# PiCam_Switch_1_2.net
KiCad netlist of a schematic drawn in EAGLE
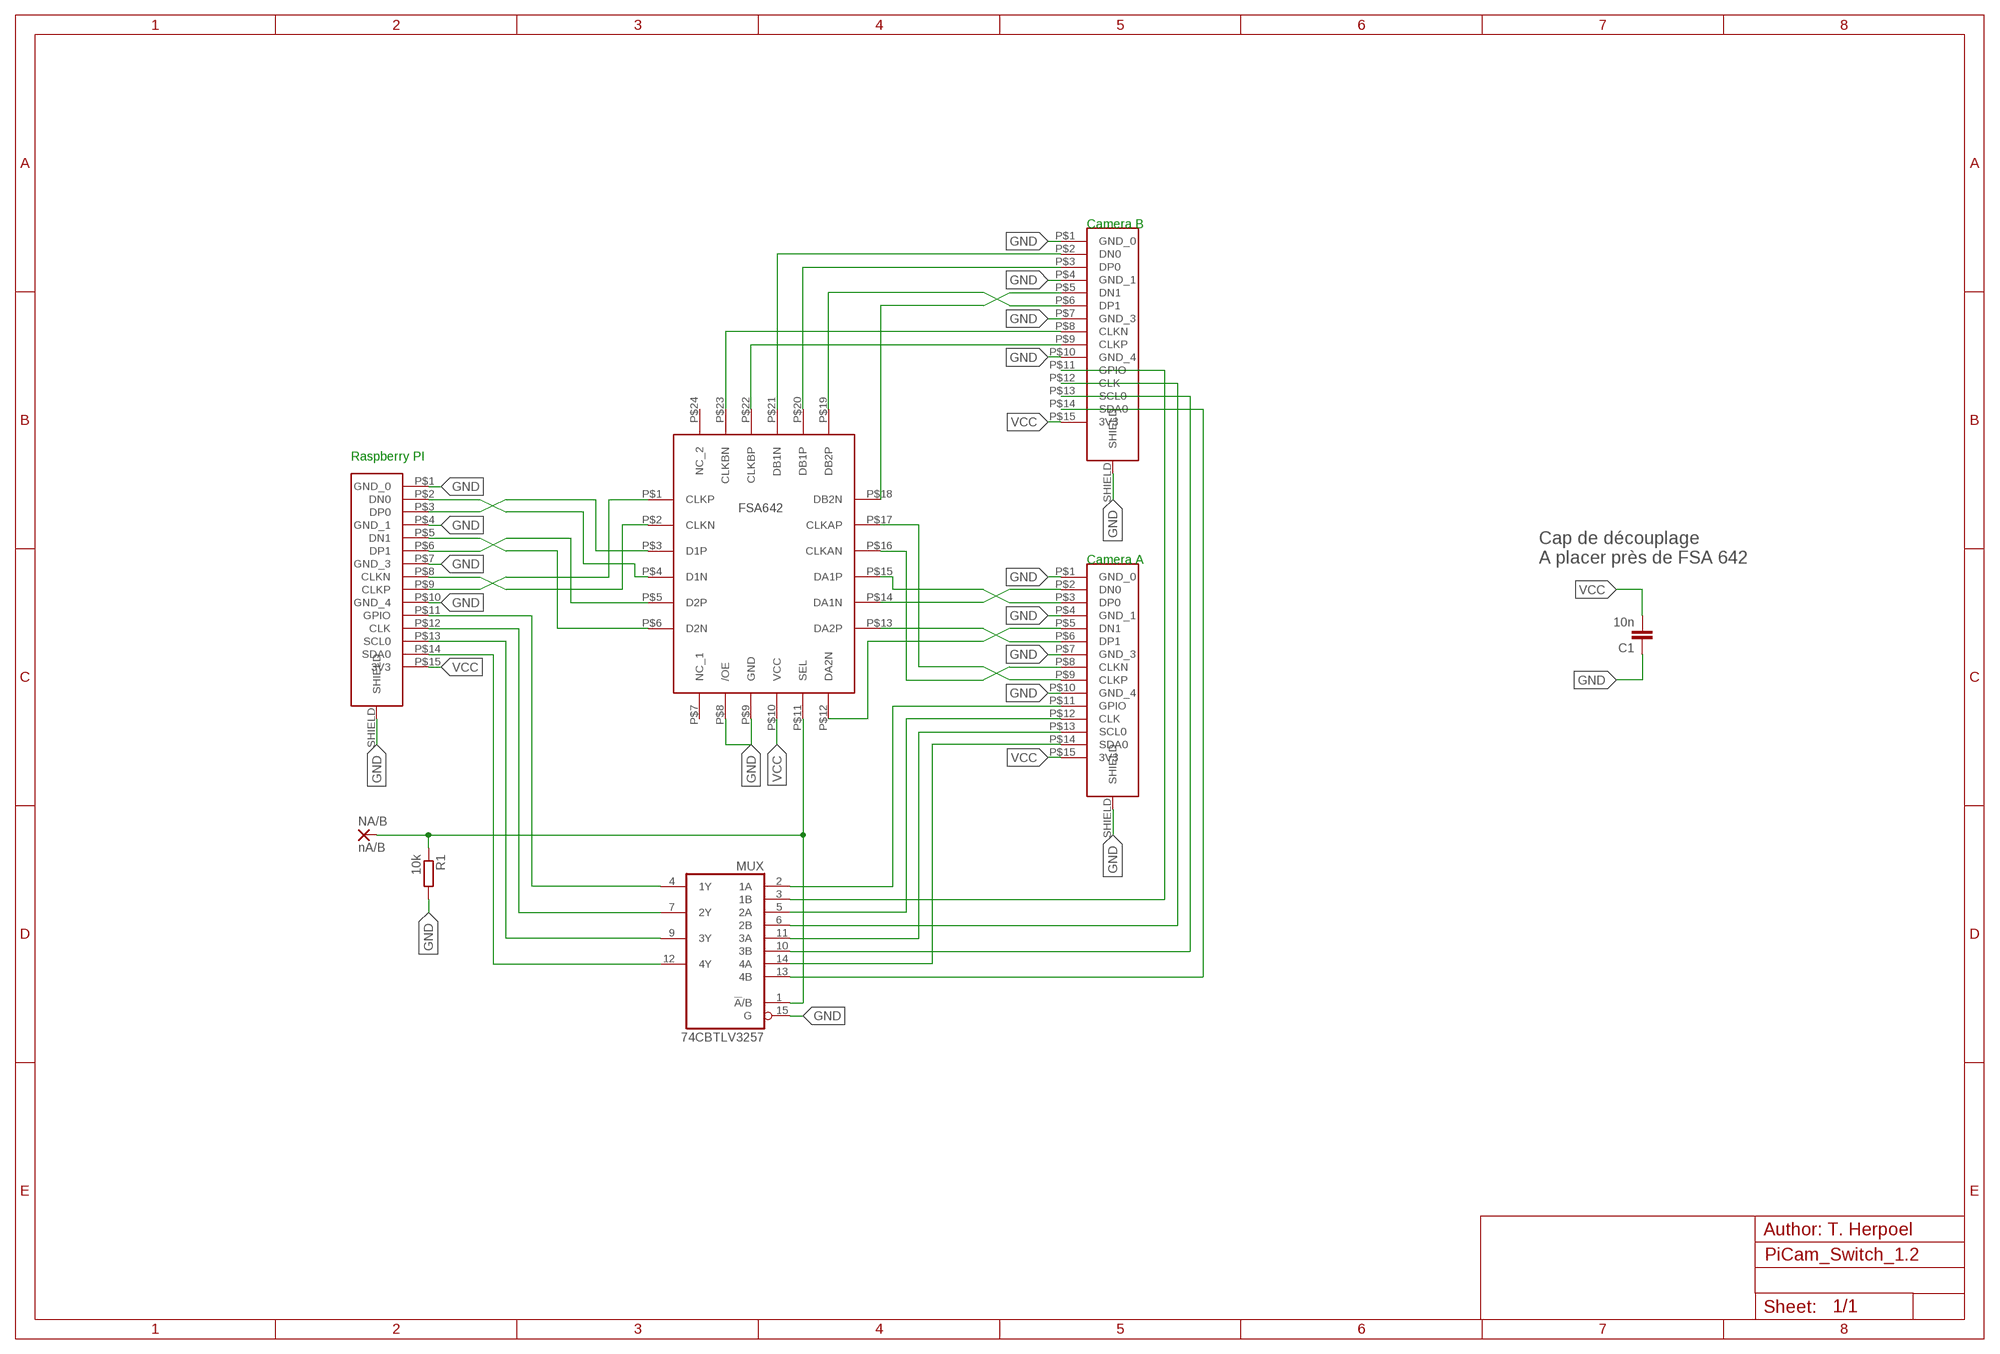
[diagram p0: schematic, sheet 1]

(export (version "E")
  (design (tool "Eeschema 10.0.6"))
  (components
    (comp (ref "C1")
      (value "10n")
      (footprint "eagle-import:C1206")
      (libsource (lib "eagle-import") (part "C-EUC1206"))
    )
    (comp (ref "CAM_A")
      (value "PICAM")
      (footprint "eagle-import:FPC-CONN-15-SMD")
      (libsource (lib "eagle-import") (part "PICAM"))
    )
    (comp (ref "CAM_B")
      (value "PICAM")
      (footprint "eagle-import:FPC-CONN-15-SMD")
      (libsource (lib "eagle-import") (part "PICAM"))
    )
    (comp (ref "MUX")
      (value "74CBTLV3257")
      (footprint "eagle-import:SO16")
      (libsource (lib "eagle-import") (part "74157DHCT"))
    )
    (comp (ref "NA/B")
      (value "nA/B")
      (footprint "eagle-import:SMD1,27-2,54")
      (libsource (lib "eagle-import") (part "SMD2"))
    )
    (comp (ref "R1")
      (value "10k")
      (footprint "eagle-import:R1206")
      (libsource (lib "eagle-import") (part "R-EU_R1206"))
    )
    (comp (ref "RPI")
      (value "PICAM")
      (footprint "eagle-import:FPC-CONN-15-SMD")
      (libsource (lib "eagle-import") (part "PICAM"))
    )
    (comp (ref "U$1")
      (value "FSA642")
      (footprint "eagle-import:UMLP-24")
      (libsource (lib "eagle-import") (part "FSA642"))
    )
  )
  (nets
    (net (code "1") (name "GND") (class "Default")
      (node (ref "C1") (pin "1") (pinfunction "1_1") (pintype "passive"))
      (node (ref "CAM_A") (pin "P$1") (pinfunction "GND_0_P$1") (pintype "bidirectional"))
      (node (ref "CAM_A") (pin "P$10") (pinfunction "GND_4_P$10") (pintype "bidirectional"))
      (node (ref "CAM_A") (pin "P$4") (pinfunction "GND_1_P$4") (pintype "bidirectional"))
      (node (ref "CAM_A") (pin "P$7") (pinfunction "GND_3_P$7") (pintype "bidirectional"))
      (node (ref "CAM_A") (pin "SHIELD") (pinfunction "SHIELD_SHIELD") (pintype "bidirectional"))
      (node (ref "CAM_B") (pin "P$1") (pinfunction "GND_0_P$1") (pintype "bidirectional"))
      (node (ref "CAM_B") (pin "P$10") (pinfunction "GND_4_P$10") (pintype "bidirectional"))
      (node (ref "CAM_B") (pin "P$4") (pinfunction "GND_1_P$4") (pintype "bidirectional"))
      (node (ref "CAM_B") (pin "P$7") (pinfunction "GND_3_P$7") (pintype "bidirectional"))
      (node (ref "CAM_B") (pin "SHIELD") (pinfunction "SHIELD_SHIELD") (pintype "bidirectional"))
      (node (ref "MUX") (pin "15") (pinfunction "G_15") (pintype "input"))
      (node (ref "R1") (pin "2") (pinfunction "2_2") (pintype "passive"))
      (node (ref "RPI") (pin "P$1") (pinfunction "GND_0_P$1") (pintype "bidirectional"))
      (node (ref "RPI") (pin "P$10") (pinfunction "GND_4_P$10") (pintype "bidirectional"))
      (node (ref "RPI") (pin "P$4") (pinfunction "GND_1_P$4") (pintype "bidirectional"))
      (node (ref "RPI") (pin "P$7") (pinfunction "GND_3_P$7") (pintype "bidirectional"))
      (node (ref "RPI") (pin "SHIELD") (pinfunction "SHIELD_SHIELD") (pintype "bidirectional"))
      (node (ref "U$1") (pin "P$8") (pinfunction "/OE_P$8") (pintype "bidirectional"))
      (node (ref "U$1") (pin "P$9") (pinfunction "GND_P$9") (pintype "bidirectional"))
    )
    (net (code "2") (name "Net-(CAM_A-CLK)") (class "Default")
      (node (ref "CAM_A") (pin "P$12") (pinfunction "CLK_P$12") (pintype "bidirectional"))
      (node (ref "MUX") (pin "5") (pinfunction "2A_5") (pintype "input"))
    )
    (net (code "3") (name "Net-(CAM_A-CLKN)") (class "Default")
      (node (ref "CAM_A") (pin "P$8") (pinfunction "CLKN_P$8") (pintype "bidirectional"))
      (node (ref "U$1") (pin "P$16") (pinfunction "CLKAN_P$16") (pintype "bidirectional"))
    )
    (net (code "4") (name "Net-(CAM_A-CLKP)") (class "Default")
      (node (ref "CAM_A") (pin "P$9") (pinfunction "CLKP_P$9") (pintype "bidirectional"))
      (node (ref "U$1") (pin "P$17") (pinfunction "CLKAP_P$17") (pintype "bidirectional"))
    )
    (net (code "5") (name "Net-(CAM_A-DN0)") (class "Default")
      (node (ref "CAM_A") (pin "P$2") (pinfunction "DN0_P$2") (pintype "bidirectional"))
      (node (ref "U$1") (pin "P$14") (pinfunction "DA1N_P$14") (pintype "bidirectional"))
    )
    (net (code "6") (name "Net-(CAM_A-DN1)") (class "Default")
      (node (ref "CAM_A") (pin "P$5") (pinfunction "DN1_P$5") (pintype "bidirectional"))
      (node (ref "U$1") (pin "P$12") (pinfunction "DA2N_P$12") (pintype "bidirectional"))
    )
    (net (code "7") (name "Net-(CAM_A-DP0)") (class "Default")
      (node (ref "CAM_A") (pin "P$3") (pinfunction "DP0_P$3") (pintype "bidirectional"))
      (node (ref "U$1") (pin "P$15") (pinfunction "DA1P_P$15") (pintype "bidirectional"))
    )
    (net (code "8") (name "Net-(CAM_A-DP1)") (class "Default")
      (node (ref "CAM_A") (pin "P$6") (pinfunction "DP1_P$6") (pintype "bidirectional"))
      (node (ref "U$1") (pin "P$13") (pinfunction "DA2P_P$13") (pintype "bidirectional"))
    )
    (net (code "9") (name "Net-(CAM_A-GPIO)") (class "Default")
      (node (ref "CAM_A") (pin "P$11") (pinfunction "GPIO_P$11") (pintype "bidirectional"))
      (node (ref "MUX") (pin "2") (pinfunction "1A_2") (pintype "input"))
    )
    (net (code "10") (name "Net-(CAM_A-SCL0)") (class "Default")
      (node (ref "CAM_A") (pin "P$13") (pinfunction "SCL0_P$13") (pintype "bidirectional"))
      (node (ref "MUX") (pin "11") (pinfunction "3A_11") (pintype "input"))
    )
    (net (code "11") (name "Net-(CAM_A-SDA0)") (class "Default")
      (node (ref "CAM_A") (pin "P$14") (pinfunction "SDA0_P$14") (pintype "bidirectional"))
      (node (ref "MUX") (pin "14") (pinfunction "4A_14") (pintype "input"))
    )
    (net (code "12") (name "Net-(CAM_B-CLK)") (class "Default")
      (node (ref "CAM_B") (pin "P$12") (pinfunction "CLK_P$12") (pintype "bidirectional"))
      (node (ref "MUX") (pin "6") (pinfunction "2B_6") (pintype "input"))
    )
    (net (code "13") (name "Net-(CAM_B-CLKN)") (class "Default")
      (node (ref "CAM_B") (pin "P$8") (pinfunction "CLKN_P$8") (pintype "bidirectional"))
      (node (ref "U$1") (pin "P$23") (pinfunction "CLKBN_P$23") (pintype "bidirectional"))
    )
    (net (code "14") (name "Net-(CAM_B-CLKP)") (class "Default")
      (node (ref "CAM_B") (pin "P$9") (pinfunction "CLKP_P$9") (pintype "bidirectional"))
      (node (ref "U$1") (pin "P$22") (pinfunction "CLKBP_P$22") (pintype "bidirectional"))
    )
    (net (code "15") (name "Net-(CAM_B-DN0)") (class "Default")
      (node (ref "CAM_B") (pin "P$2") (pinfunction "DN0_P$2") (pintype "bidirectional"))
      (node (ref "U$1") (pin "P$21") (pinfunction "DB1N_P$21") (pintype "bidirectional"))
    )
    (net (code "16") (name "Net-(CAM_B-DN1)") (class "Default")
      (node (ref "CAM_B") (pin "P$5") (pinfunction "DN1_P$5") (pintype "bidirectional"))
      (node (ref "U$1") (pin "P$18") (pinfunction "DB2N_P$18") (pintype "bidirectional"))
    )
    (net (code "17") (name "Net-(CAM_B-DP0)") (class "Default")
      (node (ref "CAM_B") (pin "P$3") (pinfunction "DP0_P$3") (pintype "bidirectional"))
      (node (ref "U$1") (pin "P$20") (pinfunction "DB1P_P$20") (pintype "bidirectional"))
    )
    (net (code "18") (name "Net-(CAM_B-DP1)") (class "Default")
      (node (ref "CAM_B") (pin "P$6") (pinfunction "DP1_P$6") (pintype "bidirectional"))
      (node (ref "U$1") (pin "P$19") (pinfunction "DB2P_P$19") (pintype "bidirectional"))
    )
    (net (code "19") (name "Net-(CAM_B-GPIO)") (class "Default")
      (node (ref "CAM_B") (pin "P$11") (pinfunction "GPIO_P$11") (pintype "bidirectional"))
      (node (ref "MUX") (pin "3") (pinfunction "1B_3") (pintype "input"))
    )
    (net (code "20") (name "Net-(CAM_B-SCL0)") (class "Default")
      (node (ref "CAM_B") (pin "P$13") (pinfunction "SCL0_P$13") (pintype "bidirectional"))
      (node (ref "MUX") (pin "10") (pinfunction "3B_10") (pintype "input"))
    )
    (net (code "21") (name "Net-(CAM_B-SDA0)") (class "Default")
      (node (ref "CAM_B") (pin "P$14") (pinfunction "SDA0_P$14") (pintype "bidirectional"))
      (node (ref "MUX") (pin "13") (pinfunction "4B_13") (pintype "input"))
    )
    (net (code "22") (name "Net-(MUXA-1Y)") (class "Default")
      (node (ref "MUX") (pin "4") (pinfunction "1Y_4") (pintype "output"))
      (node (ref "RPI") (pin "P$11") (pinfunction "GPIO_P$11") (pintype "bidirectional"))
    )
    (net (code "23") (name "Net-(MUXA-2Y)") (class "Default")
      (node (ref "MUX") (pin "7") (pinfunction "2Y_7") (pintype "output"))
      (node (ref "RPI") (pin "P$12") (pinfunction "CLK_P$12") (pintype "bidirectional"))
    )
    (net (code "24") (name "Net-(MUXA-3Y)") (class "Default")
      (node (ref "MUX") (pin "9") (pinfunction "3Y_9") (pintype "output"))
      (node (ref "RPI") (pin "P$13") (pinfunction "SCL0_P$13") (pintype "bidirectional"))
    )
    (net (code "25") (name "Net-(MUXA-4Y)") (class "Default")
      (node (ref "MUX") (pin "12") (pinfunction "4Y_12") (pintype "output"))
      (node (ref "RPI") (pin "P$14") (pinfunction "SDA0_P$14") (pintype "bidirectional"))
    )
    (net (code "26") (name "Net-(MUXA-~{A}{slash}B)") (class "Default")
      (node (ref "MUX") (pin "1") (pinfunction "~{A}/B_1") (pintype "input"))
      (node (ref "NA/B") (pin "1") (pinfunction "P_1") (pintype "passive"))
      (node (ref "R1") (pin "1") (pinfunction "1_1") (pintype "passive"))
      (node (ref "U$1") (pin "P$11") (pinfunction "SEL_P$11") (pintype "bidirectional"))
    )
    (net (code "27") (name "Net-(RPI-CLKN)") (class "Default")
      (node (ref "RPI") (pin "P$8") (pinfunction "CLKN_P$8") (pintype "bidirectional"))
      (node (ref "U$1") (pin "P$2") (pinfunction "CLKN_P$2") (pintype "bidirectional"))
    )
    (net (code "28") (name "Net-(RPI-CLKP)") (class "Default")
      (node (ref "RPI") (pin "P$9") (pinfunction "CLKP_P$9") (pintype "bidirectional"))
      (node (ref "U$1") (pin "P$1") (pinfunction "CLKP_P$1") (pintype "bidirectional"))
    )
    (net (code "29") (name "Net-(RPI-DN0)") (class "Default")
      (node (ref "RPI") (pin "P$2") (pinfunction "DN0_P$2") (pintype "bidirectional"))
      (node (ref "U$1") (pin "P$4") (pinfunction "D1N_P$4") (pintype "bidirectional"))
    )
    (net (code "30") (name "Net-(RPI-DN1)") (class "Default")
      (node (ref "RPI") (pin "P$5") (pinfunction "DN1_P$5") (pintype "bidirectional"))
      (node (ref "U$1") (pin "P$6") (pinfunction "D2N_P$6") (pintype "bidirectional"))
    )
    (net (code "31") (name "Net-(RPI-DP0)") (class "Default")
      (node (ref "RPI") (pin "P$3") (pinfunction "DP0_P$3") (pintype "bidirectional"))
      (node (ref "U$1") (pin "P$3") (pinfunction "D1P_P$3") (pintype "bidirectional"))
    )
    (net (code "32") (name "Net-(RPI-DP1)") (class "Default")
      (node (ref "RPI") (pin "P$6") (pinfunction "DP1_P$6") (pintype "bidirectional"))
      (node (ref "U$1") (pin "P$5") (pinfunction "D2P_P$5") (pintype "bidirectional"))
    )
    (net (code "33") (name "VCC") (class "Default")
      (node (ref "C1") (pin "2") (pinfunction "2_2") (pintype "passive"))
      (node (ref "CAM_A") (pin "P$15") (pinfunction "3V3_P$15") (pintype "bidirectional"))
      (node (ref "CAM_B") (pin "P$15") (pinfunction "3V3_P$15") (pintype "bidirectional"))
      (node (ref "RPI") (pin "P$15") (pinfunction "3V3_P$15") (pintype "bidirectional"))
      (node (ref "U$1") (pin "P$10") (pinfunction "VCC_P$10") (pintype "bidirectional"))
    )
    (net (code "34") (name "unconnected-(U$1-NC_1-PadP$7)") (class "Default")
      (node (ref "U$1") (pin "P$7") (pinfunction "NC_1_P$7") (pintype "bidirectional"))
    )
    (net (code "35") (name "unconnected-(U$1-NC_2-PadP$24)") (class "Default")
      (node (ref "U$1") (pin "P$24") (pinfunction "NC_2_P$24") (pintype "bidirectional"))
    )
  )
)
